# R2P_IR_module.net
KiCad netlist of a schematic drawn in EAGLE
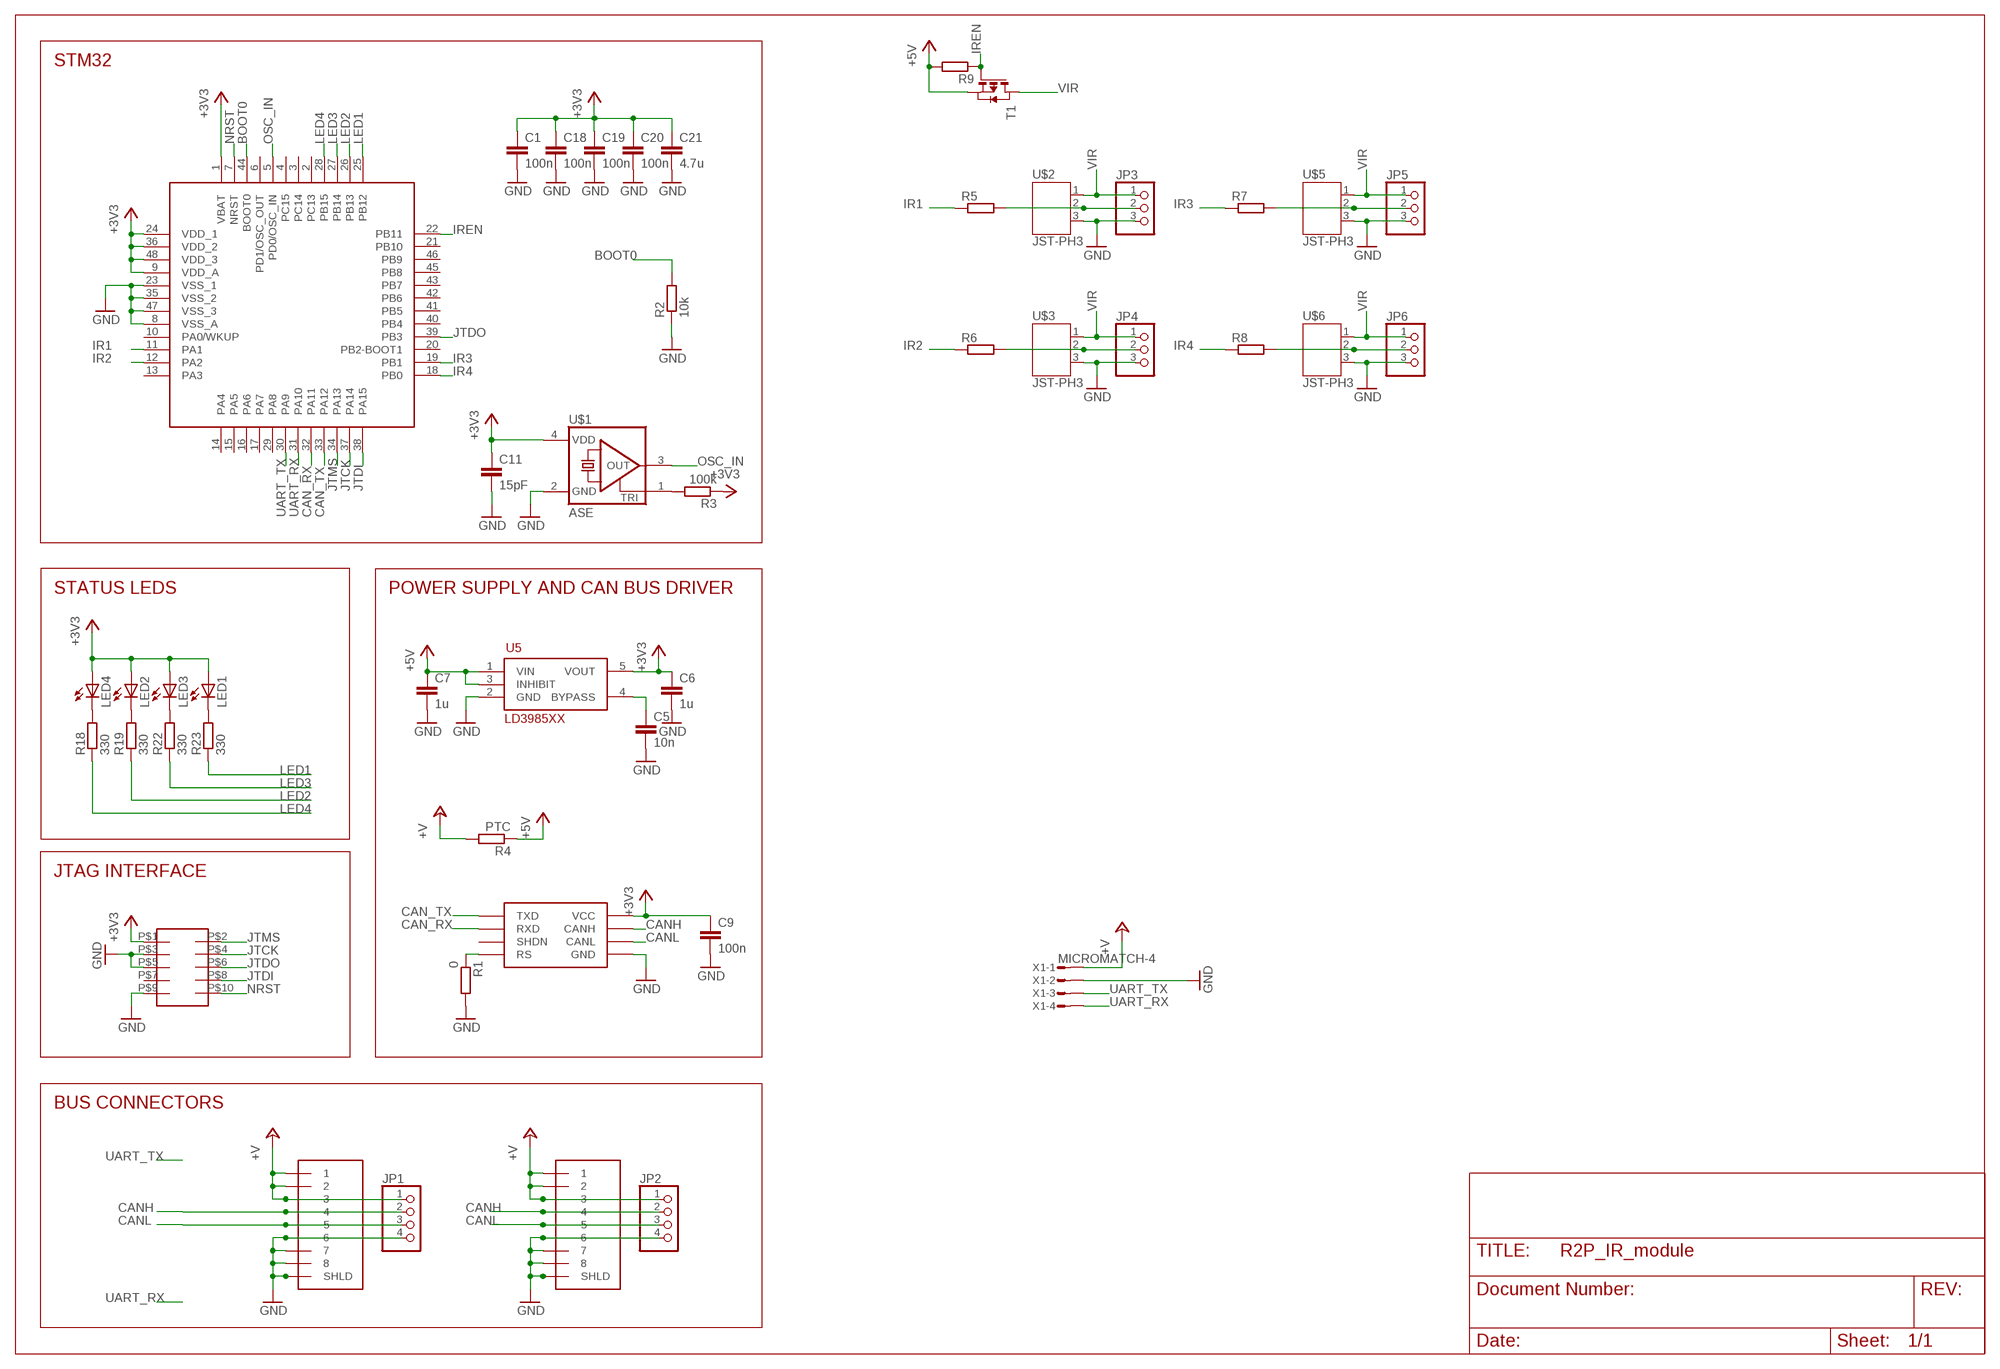
[diagram p0: schematic, sheet 1]

(export (version "E")
  (design (tool "Eeschema 10.0.6"))
  (components
    (comp (ref "1")
      (value "RJ45-43860")
      (footprint "eagle-import:0438600010")
      (libsource (lib "eagle-import") (part "RJ45-43860"))
    )
    (comp (ref "2")
      (value "RJ45-43860")
      (footprint "eagle-import:0438600010")
      (libsource (lib "eagle-import") (part "RJ45-43860"))
    )
    (comp (ref "C1")
      (value "100n")
      (footprint "eagle-import:C0603")
      (libsource (lib "eagle-import") (part "C-EUC0603"))
    )
    (comp (ref "C5")
      (value "10n")
      (footprint "eagle-import:C0603")
      (libsource (lib "eagle-import") (part "C-EUC0603"))
    )
    (comp (ref "C6")
      (value "1u")
      (footprint "eagle-import:C0603")
      (libsource (lib "eagle-import") (part "C-EUC0603"))
    )
    (comp (ref "C7")
      (value "1u")
      (footprint "eagle-import:C0603")
      (libsource (lib "eagle-import") (part "C-EUC0603"))
    )
    (comp (ref "C9")
      (value "100n")
      (footprint "eagle-import:C0603")
      (libsource (lib "eagle-import") (part "C-EUC0603"))
    )
    (comp (ref "C11")
      (value "15pF")
      (footprint "eagle-import:C0603")
      (libsource (lib "eagle-import") (part "C-EUC0603"))
    )
    (comp (ref "C18")
      (value "100n")
      (footprint "eagle-import:C0603")
      (libsource (lib "eagle-import") (part "C-EUC0603"))
    )
    (comp (ref "C19")
      (value "100n")
      (footprint "eagle-import:C0603")
      (libsource (lib "eagle-import") (part "C-EUC0603"))
    )
    (comp (ref "C20")
      (value "100n")
      (footprint "eagle-import:C0603")
      (libsource (lib "eagle-import") (part "C-EUC0603"))
    )
    (comp (ref "C21")
      (value "4.7u")
      (footprint "eagle-import:C0805")
      (libsource (lib "eagle-import") (part "C-EUC0805"))
    )
    (comp (ref "JP1")
      (value "PINHD-1X4")
      (footprint "eagle-import:1X04")
      (libsource (lib "eagle-import") (part "PINHD-1X4"))
    )
    (comp (ref "JP2")
      (value "PINHD-1X4")
      (footprint "eagle-import:1X04")
      (libsource (lib "eagle-import") (part "PINHD-1X4"))
    )
    (comp (ref "JP3")
      (value "PINHD-1X3")
      (footprint "eagle-import:1X03")
      (libsource (lib "eagle-import") (part "PINHD-1X3"))
    )
    (comp (ref "JP4")
      (value "PINHD-1X3")
      (footprint "eagle-import:1X03")
      (libsource (lib "eagle-import") (part "PINHD-1X3"))
    )
    (comp (ref "JP5")
      (value "PINHD-1X3")
      (footprint "eagle-import:1X03")
      (libsource (lib "eagle-import") (part "PINHD-1X3"))
    )
    (comp (ref "JP6")
      (value "PINHD-1X3")
      (footprint "eagle-import:1X03")
      (libsource (lib "eagle-import") (part "PINHD-1X3"))
    )
    (comp (ref "LED1")
      (value "LEDCHIPLED_0805")
      (footprint "eagle-import:CHIPLED_0805")
      (libsource (lib "eagle-import") (part "LEDCHIPLED_0805"))
    )
    (comp (ref "LED2")
      (value "LEDCHIPLED_0805")
      (footprint "eagle-import:CHIPLED_0805")
      (libsource (lib "eagle-import") (part "LEDCHIPLED_0805"))
    )
    (comp (ref "LED3")
      (value "LEDCHIPLED_0805")
      (footprint "eagle-import:CHIPLED_0805")
      (libsource (lib "eagle-import") (part "LEDCHIPLED_0805"))
    )
    (comp (ref "LED4")
      (value "LEDCHIPLED_0805")
      (footprint "eagle-import:CHIPLED_0805")
      (libsource (lib "eagle-import") (part "LEDCHIPLED_0805"))
    )
    (comp (ref "R1")
      (value "0")
      (footprint "eagle-import:R0603")
      (libsource (lib "eagle-import") (part "R-EU_R0603"))
    )
    (comp (ref "R2")
      (value "10k")
      (footprint "eagle-import:R0603")
      (libsource (lib "eagle-import") (part "R-EU_R0603"))
    )
    (comp (ref "R3")
      (value "100k")
      (footprint "eagle-import:R0603")
      (libsource (lib "eagle-import") (part "R-EU_R0603"))
    )
    (comp (ref "R4")
      (value "PTC")
      (footprint "eagle-import:R0603")
      (libsource (lib "eagle-import") (part "R-EU_R0603"))
    )
    (comp (ref "R5")
      (value "R-EU_R0603")
      (footprint "eagle-import:R0603")
      (libsource (lib "eagle-import") (part "R-EU_R0603"))
    )
    (comp (ref "R6")
      (value "R-EU_R0603")
      (footprint "eagle-import:R0603")
      (libsource (lib "eagle-import") (part "R-EU_R0603"))
    )
    (comp (ref "R7")
      (value "R-EU_R0603")
      (footprint "eagle-import:R0603")
      (libsource (lib "eagle-import") (part "R-EU_R0603"))
    )
    (comp (ref "R8")
      (value "R-EU_R0603")
      (footprint "eagle-import:R0603")
      (libsource (lib "eagle-import") (part "R-EU_R0603"))
    )
    (comp (ref "R9")
      (value "R-EU_R0603")
      (footprint "eagle-import:R0603")
      (libsource (lib "eagle-import") (part "R-EU_R0603"))
    )
    (comp (ref "R18")
      (value "330")
      (footprint "eagle-import:R0603")
      (libsource (lib "eagle-import") (part "R-EU_R0603"))
    )
    (comp (ref "R19")
      (value "330")
      (footprint "eagle-import:R0603")
      (libsource (lib "eagle-import") (part "R-EU_R0603"))
    )
    (comp (ref "R22")
      (value "330")
      (footprint "eagle-import:R0603")
      (libsource (lib "eagle-import") (part "R-EU_R0603"))
    )
    (comp (ref "R23")
      (value "330")
      (footprint "eagle-import:R0603")
      (libsource (lib "eagle-import") (part "R-EU_R0603"))
    )
    (comp (ref "SOT1")
      (value "MAX3051")
      (footprint "eagle-import:SOT23-8L")
      (libsource (lib "eagle-import") (part "MAX3051"))
    )
    (comp (ref "T1")
      (value "PMOSSOT23")
      (footprint "eagle-import:SOT-23")
      (libsource (lib "eagle-import") (part "PMOSSOT23"))
    )
    (comp (ref "U$1")
      (value "ASE")
      (footprint "eagle-import:ASE")
      (libsource (lib "eagle-import") (part "ASE"))
    )
    (comp (ref "U$2")
      (value "JST-PH3")
      (footprint "eagle-import:JST-PH3")
      (libsource (lib "eagle-import") (part "JST-PH3"))
    )
    (comp (ref "U$3")
      (value "JST-PH3")
      (footprint "eagle-import:JST-PH3")
      (libsource (lib "eagle-import") (part "JST-PH3"))
    )
    (comp (ref "U$4")
      (value "FTSH-105")
      (footprint "eagle-import:FTSH-105")
      (libsource (lib "eagle-import") (part "FTSH-105"))
    )
    (comp (ref "U$5")
      (value "JST-PH3")
      (footprint "eagle-import:JST-PH3")
      (libsource (lib "eagle-import") (part "JST-PH3"))
    )
    (comp (ref "U$6")
      (value "JST-PH3")
      (footprint "eagle-import:JST-PH3")
      (libsource (lib "eagle-import") (part "JST-PH3"))
    )
    (comp (ref "U1")
      (value "STM32F103CX")
      (footprint "eagle-import:LQFP48")
      (libsource (lib "eagle-import") (part "STM32F103CX"))
    )
    (comp (ref "U5")
      (value "LD3985XX")
      (footprint "eagle-import:SOT23-5L")
      (libsource (lib "eagle-import") (part "LD3985XX"))
    )
    (comp (ref "X1")
      (value "MICROMATCH-4")
      (footprint "eagle-import:MICROMATCH-4")
      (libsource (lib "eagle-import") (part "MICROMATCH-4"))
    )
  )
  (nets
    (net (code "1") (name "+3V3") (class "Default")
      (node (ref "C1") (pin "1") (pinfunction "1_1") (pintype "passive"))
      (node (ref "C11") (pin "1") (pinfunction "1_1") (pintype "passive"))
      (node (ref "C18") (pin "1") (pinfunction "1_1") (pintype "passive"))
      (node (ref "C19") (pin "1") (pinfunction "1_1") (pintype "passive"))
      (node (ref "C20") (pin "1") (pinfunction "1_1") (pintype "passive"))
      (node (ref "C21") (pin "1") (pinfunction "1_1") (pintype "passive"))
      (node (ref "C6") (pin "1") (pinfunction "1_1") (pintype "passive"))
      (node (ref "C9") (pin "1") (pinfunction "1_1") (pintype "passive"))
      (node (ref "LED1") (pin "A") (pinfunction "A_A") (pintype "passive"))
      (node (ref "LED2") (pin "A") (pinfunction "A_A") (pintype "passive"))
      (node (ref "LED3") (pin "A") (pinfunction "A_A") (pintype "passive"))
      (node (ref "LED4") (pin "A") (pinfunction "A_A") (pintype "passive"))
      (node (ref "R3") (pin "1") (pinfunction "1_1") (pintype "passive"))
      (node (ref "SOT1") (pin "P$3") (pinfunction "VCC_P$3") (pintype "bidirectional"))
      (node (ref "U$1") (pin "4") (pinfunction "VDD_4") (pintype "power_in"))
      (node (ref "U$4") (pin "P$1") (pinfunction "P$1_P$1") (pintype "bidirectional"))
      (node (ref "U1") (pin "1") (pinfunction "VBAT_1") (pintype "bidirectional"))
      (node (ref "U1") (pin "24") (pinfunction "VDD_1_24") (pintype "bidirectional"))
      (node (ref "U1") (pin "36") (pinfunction "VDD_2_36") (pintype "bidirectional"))
      (node (ref "U1") (pin "48") (pinfunction "VDD_3_48") (pintype "bidirectional"))
      (node (ref "U1") (pin "9") (pinfunction "VDD_A_9") (pintype "bidirectional"))
      (node (ref "U5") (pin "5") (pinfunction "VOUT_5") (pintype "bidirectional"))
    )
    (net (code "2") (name "+5V") (class "Default")
      (node (ref "C7") (pin "1") (pinfunction "1_1") (pintype "passive"))
      (node (ref "R4") (pin "1") (pinfunction "1_1") (pintype "passive"))
      (node (ref "R9") (pin "2") (pinfunction "2_2") (pintype "passive"))
      (node (ref "T1") (pin "2") (pinfunction "S_2") (pintype "passive"))
      (node (ref "U5") (pin "1") (pinfunction "VIN_1") (pintype "bidirectional"))
      (node (ref "U5") (pin "3") (pinfunction "INHIBIT_3") (pintype "bidirectional"))
    )
    (net (code "3") (name "+V") (class "Default")
      (node (ref "1") (pin "P$1") (pinfunction "1_P$1") (pintype "bidirectional"))
      (node (ref "1") (pin "P$2") (pinfunction "2_P$2") (pintype "bidirectional"))
      (node (ref "1") (pin "P$3") (pinfunction "3_P$3") (pintype "bidirectional"))
      (node (ref "2") (pin "P$1") (pinfunction "1_P$1") (pintype "bidirectional"))
      (node (ref "2") (pin "P$2") (pinfunction "2_P$2") (pintype "bidirectional"))
      (node (ref "2") (pin "P$3") (pinfunction "3_P$3") (pintype "bidirectional"))
      (node (ref "JP1") (pin "1") (pinfunction "1_1") (pintype "passive"))
      (node (ref "JP2") (pin "1") (pinfunction "1_1") (pintype "passive"))
      (node (ref "R4") (pin "2") (pinfunction "2_2") (pintype "passive"))
      (node (ref "X1") (pin "1") (pinfunction "S_1") (pintype "passive"))
    )
    (net (code "4") (name "/BOOT0") (class "Default")
      (node (ref "R2") (pin "2") (pinfunction "2_2") (pintype "passive"))
      (node (ref "U1") (pin "44") (pinfunction "BOOT0_44") (pintype "bidirectional"))
    )
    (net (code "5") (name "/CANH") (class "Default")
      (node (ref "1") (pin "P$4") (pinfunction "4_P$4") (pintype "bidirectional"))
      (node (ref "2") (pin "P$4") (pinfunction "4_P$4") (pintype "bidirectional"))
      (node (ref "JP1") (pin "2") (pinfunction "2_2") (pintype "passive"))
      (node (ref "JP2") (pin "2") (pinfunction "2_2") (pintype "passive"))
      (node (ref "SOT1") (pin "P$7") (pinfunction "CANH_P$7") (pintype "bidirectional"))
    )
    (net (code "6") (name "/CANL") (class "Default")
      (node (ref "1") (pin "P$5") (pinfunction "5_P$5") (pintype "bidirectional"))
      (node (ref "2") (pin "P$5") (pinfunction "5_P$5") (pintype "bidirectional"))
      (node (ref "JP1") (pin "3") (pinfunction "3_3") (pintype "passive"))
      (node (ref "JP2") (pin "3") (pinfunction "3_3") (pintype "passive"))
      (node (ref "SOT1") (pin "P$6") (pinfunction "CANL_P$6") (pintype "bidirectional"))
    )
    (net (code "7") (name "/CAN_RX") (class "Default")
      (node (ref "SOT1") (pin "P$4") (pinfunction "RXD_P$4") (pintype "bidirectional"))
      (node (ref "U1") (pin "32") (pinfunction "PA11_32") (pintype "bidirectional"))
    )
    (net (code "8") (name "/CAN_TX") (class "Default")
      (node (ref "SOT1") (pin "P$1") (pinfunction "TXD_P$1") (pintype "bidirectional"))
      (node (ref "U1") (pin "33") (pinfunction "PA12_33") (pintype "bidirectional"))
    )
    (net (code "9") (name "/IR1") (class "Default")
      (node (ref "R5") (pin "1") (pinfunction "1_1") (pintype "passive"))
      (node (ref "U1") (pin "11") (pinfunction "PA1_11") (pintype "bidirectional"))
    )
    (net (code "10") (name "/IR2") (class "Default")
      (node (ref "R6") (pin "1") (pinfunction "1_1") (pintype "passive"))
      (node (ref "U1") (pin "12") (pinfunction "PA2_12") (pintype "bidirectional"))
    )
    (net (code "11") (name "/IR3") (class "Default")
      (node (ref "R7") (pin "1") (pinfunction "1_1") (pintype "passive"))
      (node (ref "U1") (pin "19") (pinfunction "PB1_19") (pintype "bidirectional"))
    )
    (net (code "12") (name "/IR4") (class "Default")
      (node (ref "R8") (pin "1") (pinfunction "1_1") (pintype "passive"))
      (node (ref "U1") (pin "18") (pinfunction "PB0_18") (pintype "bidirectional"))
    )
    (net (code "13") (name "/IREN") (class "Default")
      (node (ref "R9") (pin "1") (pinfunction "1_1") (pintype "passive"))
      (node (ref "T1") (pin "3") (pinfunction "G_3") (pintype "passive"))
      (node (ref "U1") (pin "22") (pinfunction "PB11_22") (pintype "bidirectional"))
    )
    (net (code "14") (name "/JTCK") (class "Default")
      (node (ref "U$4") (pin "P$4") (pinfunction "P$4_P$4") (pintype "bidirectional"))
      (node (ref "U1") (pin "37") (pinfunction "PA14_37") (pintype "bidirectional"))
    )
    (net (code "15") (name "/JTDI") (class "Default")
      (node (ref "U$4") (pin "P$8") (pinfunction "P$8_P$8") (pintype "bidirectional"))
      (node (ref "U1") (pin "38") (pinfunction "PA15_38") (pintype "bidirectional"))
    )
    (net (code "16") (name "/JTDO") (class "Default")
      (node (ref "U$4") (pin "P$6") (pinfunction "P$6_P$6") (pintype "bidirectional"))
      (node (ref "U1") (pin "39") (pinfunction "PB3_39") (pintype "bidirectional"))
    )
    (net (code "17") (name "/JTMS") (class "Default")
      (node (ref "U$4") (pin "P$2") (pinfunction "P$2_P$2") (pintype "bidirectional"))
      (node (ref "U1") (pin "34") (pinfunction "PA13_34") (pintype "bidirectional"))
    )
    (net (code "18") (name "/LED1") (class "Default")
      (node (ref "R23") (pin "1") (pinfunction "1_1") (pintype "passive"))
      (node (ref "U1") (pin "25") (pinfunction "PB12_25") (pintype "bidirectional"))
    )
    (net (code "19") (name "/LED2") (class "Default")
      (node (ref "R19") (pin "1") (pinfunction "1_1") (pintype "passive"))
      (node (ref "U1") (pin "26") (pinfunction "PB13_26") (pintype "bidirectional"))
    )
    (net (code "20") (name "/LED3") (class "Default")
      (node (ref "R22") (pin "1") (pinfunction "1_1") (pintype "passive"))
      (node (ref "U1") (pin "27") (pinfunction "PB14_27") (pintype "bidirectional"))
    )
    (net (code "21") (name "/LED4") (class "Default")
      (node (ref "R18") (pin "1") (pinfunction "1_1") (pintype "passive"))
      (node (ref "U1") (pin "28") (pinfunction "PB15_28") (pintype "bidirectional"))
    )
    (net (code "22") (name "/NRST") (class "Default")
      (node (ref "U$4") (pin "P$10") (pinfunction "P$10_P$10") (pintype "bidirectional"))
      (node (ref "U1") (pin "7") (pinfunction "NRST_7") (pintype "bidirectional"))
    )
    (net (code "23") (name "/OSC_IN") (class "Default")
      (node (ref "U$1") (pin "3") (pinfunction "OUT_3") (pintype "output"))
      (node (ref "U1") (pin "5") (pinfunction "PD0/OSC_IN_5") (pintype "bidirectional"))
    )
    (net (code "24") (name "/UART_RX") (class "Default")
      (node (ref "U1") (pin "31") (pinfunction "PA10_31") (pintype "bidirectional"))
      (node (ref "X1") (pin "4") (pinfunction "S_4") (pintype "passive"))
    )
    (net (code "25") (name "/UART_TX") (class "Default")
      (node (ref "U1") (pin "30") (pinfunction "PA9_30") (pintype "bidirectional"))
      (node (ref "X1") (pin "3") (pinfunction "S_3") (pintype "passive"))
    )
    (net (code "26") (name "/VIR") (class "Default")
      (node (ref "JP3") (pin "1") (pinfunction "1_1") (pintype "passive"))
      (node (ref "JP4") (pin "1") (pinfunction "1_1") (pintype "passive"))
      (node (ref "JP5") (pin "1") (pinfunction "1_1") (pintype "passive"))
      (node (ref "JP6") (pin "1") (pinfunction "1_1") (pintype "passive"))
      (node (ref "T1") (pin "1") (pinfunction "D_1") (pintype "passive"))
      (node (ref "U$2") (pin "1") (pinfunction "1_1") (pintype "passive"))
      (node (ref "U$3") (pin "1") (pinfunction "1_1") (pintype "passive"))
      (node (ref "U$5") (pin "1") (pinfunction "1_1") (pintype "passive"))
      (node (ref "U$6") (pin "1") (pinfunction "1_1") (pintype "passive"))
    )
    (net (code "27") (name "GND") (class "Default")
      (node (ref "1") (pin "P$10") (pinfunction "P$1_P$10") (pintype "power_in"))
      (node (ref "1") (pin "P$6") (pinfunction "6_P$6") (pintype "bidirectional"))
      (node (ref "1") (pin "P$7") (pinfunction "7_P$7") (pintype "bidirectional"))
      (node (ref "1") (pin "P$8") (pinfunction "8_P$8") (pintype "bidirectional"))
      (node (ref "1") (pin "P$9") (pinfunction "SHLD_P$9") (pintype "power_in"))
      (node (ref "2") (pin "P$10") (pinfunction "P$1_P$10") (pintype "power_in"))
      (node (ref "2") (pin "P$6") (pinfunction "6_P$6") (pintype "bidirectional"))
      (node (ref "2") (pin "P$7") (pinfunction "7_P$7") (pintype "bidirectional"))
      (node (ref "2") (pin "P$8") (pinfunction "8_P$8") (pintype "bidirectional"))
      (node (ref "2") (pin "P$9") (pinfunction "SHLD_P$9") (pintype "power_in"))
      (node (ref "C1") (pin "2") (pinfunction "2_2") (pintype "passive"))
      (node (ref "C11") (pin "2") (pinfunction "2_2") (pintype "passive"))
      (node (ref "C18") (pin "2") (pinfunction "2_2") (pintype "passive"))
      (node (ref "C19") (pin "2") (pinfunction "2_2") (pintype "passive"))
      (node (ref "C20") (pin "2") (pinfunction "2_2") (pintype "passive"))
      (node (ref "C21") (pin "2") (pinfunction "2_2") (pintype "passive"))
      (node (ref "C5") (pin "2") (pinfunction "2_2") (pintype "passive"))
      (node (ref "C6") (pin "2") (pinfunction "2_2") (pintype "passive"))
      (node (ref "C7") (pin "2") (pinfunction "2_2") (pintype "passive"))
      (node (ref "C9") (pin "2") (pinfunction "2_2") (pintype "passive"))
      (node (ref "JP1") (pin "4") (pinfunction "4_4") (pintype "passive"))
      (node (ref "JP2") (pin "4") (pinfunction "4_4") (pintype "passive"))
      (node (ref "JP3") (pin "3") (pinfunction "3_3") (pintype "passive"))
      (node (ref "JP4") (pin "3") (pinfunction "3_3") (pintype "passive"))
      (node (ref "JP5") (pin "3") (pinfunction "3_3") (pintype "passive"))
      (node (ref "JP6") (pin "3") (pinfunction "3_3") (pintype "passive"))
      (node (ref "R1") (pin "2") (pinfunction "2_2") (pintype "passive"))
      (node (ref "R2") (pin "1") (pinfunction "1_1") (pintype "passive"))
      (node (ref "SOT1") (pin "P$2") (pinfunction "GND_P$2") (pintype "bidirectional"))
      (node (ref "U$1") (pin "2") (pinfunction "GND_2") (pintype "power_in"))
      (node (ref "U$2") (pin "3") (pinfunction "3_3") (pintype "passive"))
      (node (ref "U$3") (pin "3") (pinfunction "3_3") (pintype "passive"))
      (node (ref "U$4") (pin "P$3") (pinfunction "P$3_P$3") (pintype "bidirectional"))
      (node (ref "U$4") (pin "P$5") (pinfunction "P$5_P$5") (pintype "bidirectional"))
      (node (ref "U$4") (pin "P$9") (pinfunction "P$9_P$9") (pintype "bidirectional"))
      (node (ref "U$5") (pin "3") (pinfunction "3_3") (pintype "passive"))
      (node (ref "U$6") (pin "3") (pinfunction "3_3") (pintype "passive"))
      (node (ref "U1") (pin "23") (pinfunction "VSS_1_23") (pintype "bidirectional"))
      (node (ref "U1") (pin "35") (pinfunction "VSS_2_35") (pintype "bidirectional"))
      (node (ref "U1") (pin "47") (pinfunction "VSS_3_47") (pintype "bidirectional"))
      (node (ref "U1") (pin "8") (pinfunction "VSS_A_8") (pintype "bidirectional"))
      (node (ref "U5") (pin "2") (pinfunction "GND_2") (pintype "bidirectional"))
      (node (ref "X1") (pin "2") (pinfunction "S_2") (pintype "passive"))
    )
    (net (code "28") (name "Net-(JP3-Pad2)") (class "Default")
      (node (ref "JP3") (pin "2") (pinfunction "2_2") (pintype "passive"))
      (node (ref "R5") (pin "2") (pinfunction "2_2") (pintype "passive"))
      (node (ref "U$2") (pin "2") (pinfunction "2_2") (pintype "passive"))
    )
    (net (code "29") (name "Net-(JP4-Pad2)") (class "Default")
      (node (ref "JP4") (pin "2") (pinfunction "2_2") (pintype "passive"))
      (node (ref "R6") (pin "2") (pinfunction "2_2") (pintype "passive"))
      (node (ref "U$3") (pin "2") (pinfunction "2_2") (pintype "passive"))
    )
    (net (code "30") (name "Net-(JP5-Pad2)") (class "Default")
      (node (ref "JP5") (pin "2") (pinfunction "2_2") (pintype "passive"))
      (node (ref "R7") (pin "2") (pinfunction "2_2") (pintype "passive"))
      (node (ref "U$5") (pin "2") (pinfunction "2_2") (pintype "passive"))
    )
    (net (code "31") (name "Net-(JP6-Pad2)") (class "Default")
      (node (ref "JP6") (pin "2") (pinfunction "2_2") (pintype "passive"))
      (node (ref "R8") (pin "2") (pinfunction "2_2") (pintype "passive"))
      (node (ref "U$6") (pin "2") (pinfunction "2_2") (pintype "passive"))
    )
    (net (code "32") (name "Net-(LED1-PadC)") (class "Default")
      (node (ref "LED1") (pin "C") (pinfunction "C_C") (pintype "passive"))
      (node (ref "R23") (pin "2") (pinfunction "2_2") (pintype "passive"))
    )
    (net (code "33") (name "Net-(LED2-PadC)") (class "Default")
      (node (ref "LED2") (pin "C") (pinfunction "C_C") (pintype "passive"))
      (node (ref "R19") (pin "2") (pinfunction "2_2") (pintype "passive"))
    )
    (net (code "34") (name "Net-(LED3-PadC)") (class "Default")
      (node (ref "LED3") (pin "C") (pinfunction "C_C") (pintype "passive"))
      (node (ref "R22") (pin "2") (pinfunction "2_2") (pintype "passive"))
    )
    (net (code "35") (name "Net-(LED4-PadC)") (class "Default")
      (node (ref "LED4") (pin "C") (pinfunction "C_C") (pintype "passive"))
      (node (ref "R18") (pin "2") (pinfunction "2_2") (pintype "passive"))
    )
    (net (code "36") (name "Net-(SOT1-RS)") (class "Default")
      (node (ref "R1") (pin "1") (pinfunction "1_1") (pintype "passive"))
      (node (ref "SOT1") (pin "P$8") (pinfunction "RS_P$8") (pintype "bidirectional"))
    )
    (net (code "37") (name "Net-(U$1-TRI)") (class "Default")
      (node (ref "R3") (pin "2") (pinfunction "2_2") (pintype "passive"))
      (node (ref "U$1") (pin "1") (pinfunction "TRI_1") (pintype "input"))
    )
    (net (code "38") (name "Net-(U5-BYPASS)") (class "Default")
      (node (ref "C5") (pin "1") (pinfunction "1_1") (pintype "passive"))
      (node (ref "U5") (pin "4") (pinfunction "BYPASS_4") (pintype "bidirectional"))
    )
    (net (code "39") (name "unconnected-(SOT1-SHDN-PadP$5)") (class "Default")
      (node (ref "SOT1") (pin "P$5") (pinfunction "SHDN_P$5") (pintype "bidirectional"))
    )
    (net (code "40") (name "unconnected-(U$4-PadP$7)") (class "Default")
      (node (ref "U$4") (pin "P$7") (pinfunction "P$7_P$7") (pintype "bidirectional"))
    )
    (net (code "41") (name "unconnected-(U1-PA0{slash}WKUP-Pad10)") (class "Default")
      (node (ref "U1") (pin "10") (pinfunction "PA0/WKUP_10") (pintype "bidirectional"))
    )
    (net (code "42") (name "unconnected-(U1-PA3-Pad13)") (class "Default")
      (node (ref "U1") (pin "13") (pinfunction "PA3_13") (pintype "bidirectional"))
    )
    (net (code "43") (name "unconnected-(U1-PA4-Pad14)") (class "Default")
      (node (ref "U1") (pin "14") (pinfunction "PA4_14") (pintype "bidirectional"))
    )
    (net (code "44") (name "unconnected-(U1-PA5-Pad15)") (class "Default")
      (node (ref "U1") (pin "15") (pinfunction "PA5_15") (pintype "bidirectional"))
    )
    (net (code "45") (name "unconnected-(U1-PA6-Pad16)") (class "Default")
      (node (ref "U1") (pin "16") (pinfunction "PA6_16") (pintype "bidirectional"))
    )
    (net (code "46") (name "unconnected-(U1-PA7-Pad17)") (class "Default")
      (node (ref "U1") (pin "17") (pinfunction "PA7_17") (pintype "bidirectional"))
    )
    (net (code "47") (name "unconnected-(U1-PA8-Pad29)") (class "Default")
      (node (ref "U1") (pin "29") (pinfunction "PA8_29") (pintype "bidirectional"))
    )
    (net (code "48") (name "unconnected-(U1-PB2-BOOT1-Pad20)") (class "Default")
      (node (ref "U1") (pin "20") (pinfunction "PB2-BOOT1_20") (pintype "bidirectional"))
    )
    (net (code "49") (name "unconnected-(U1-PB4-Pad40)") (class "Default")
      (node (ref "U1") (pin "40") (pinfunction "PB4_40") (pintype "bidirectional"))
    )
    (net (code "50") (name "unconnected-(U1-PB5-Pad41)") (class "Default")
      (node (ref "U1") (pin "41") (pinfunction "PB5_41") (pintype "bidirectional"))
    )
    (net (code "51") (name "unconnected-(U1-PB6-Pad42)") (class "Default")
      (node (ref "U1") (pin "42") (pinfunction "PB6_42") (pintype "bidirectional"))
    )
    (net (code "52") (name "unconnected-(U1-PB7-Pad43)") (class "Default")
      (node (ref "U1") (pin "43") (pinfunction "PB7_43") (pintype "bidirectional"))
    )
    (net (code "53") (name "unconnected-(U1-PB8-Pad45)") (class "Default")
      (node (ref "U1") (pin "45") (pinfunction "PB8_45") (pintype "bidirectional"))
    )
    (net (code "54") (name "unconnected-(U1-PB9-Pad46)") (class "Default")
      (node (ref "U1") (pin "46") (pinfunction "PB9_46") (pintype "bidirectional"))
    )
    (net (code "55") (name "unconnected-(U1-PB10-Pad21)") (class "Default")
      (node (ref "U1") (pin "21") (pinfunction "PB10_21") (pintype "bidirectional"))
    )
    (net (code "56") (name "unconnected-(U1-PC13-Pad2)") (class "Default")
      (node (ref "U1") (pin "2") (pinfunction "PC13_2") (pintype "bidirectional"))
    )
    (net (code "57") (name "unconnected-(U1-PC14-Pad3)") (class "Default")
      (node (ref "U1") (pin "3") (pinfunction "PC14_3") (pintype "bidirectional"))
    )
    (net (code "58") (name "unconnected-(U1-PC15-Pad4)") (class "Default")
      (node (ref "U1") (pin "4") (pinfunction "PC15_4") (pintype "bidirectional"))
    )
    (net (code "59") (name "unconnected-(U1-PD1{slash}OSC_OUT-Pad6)") (class "Default")
      (node (ref "U1") (pin "6") (pinfunction "PD1/OSC_OUT_6") (pintype "bidirectional"))
    )
  )
)
